# Bi-Quad_Filter.net
KiCad netlist of a schematic drawn in EAGLE
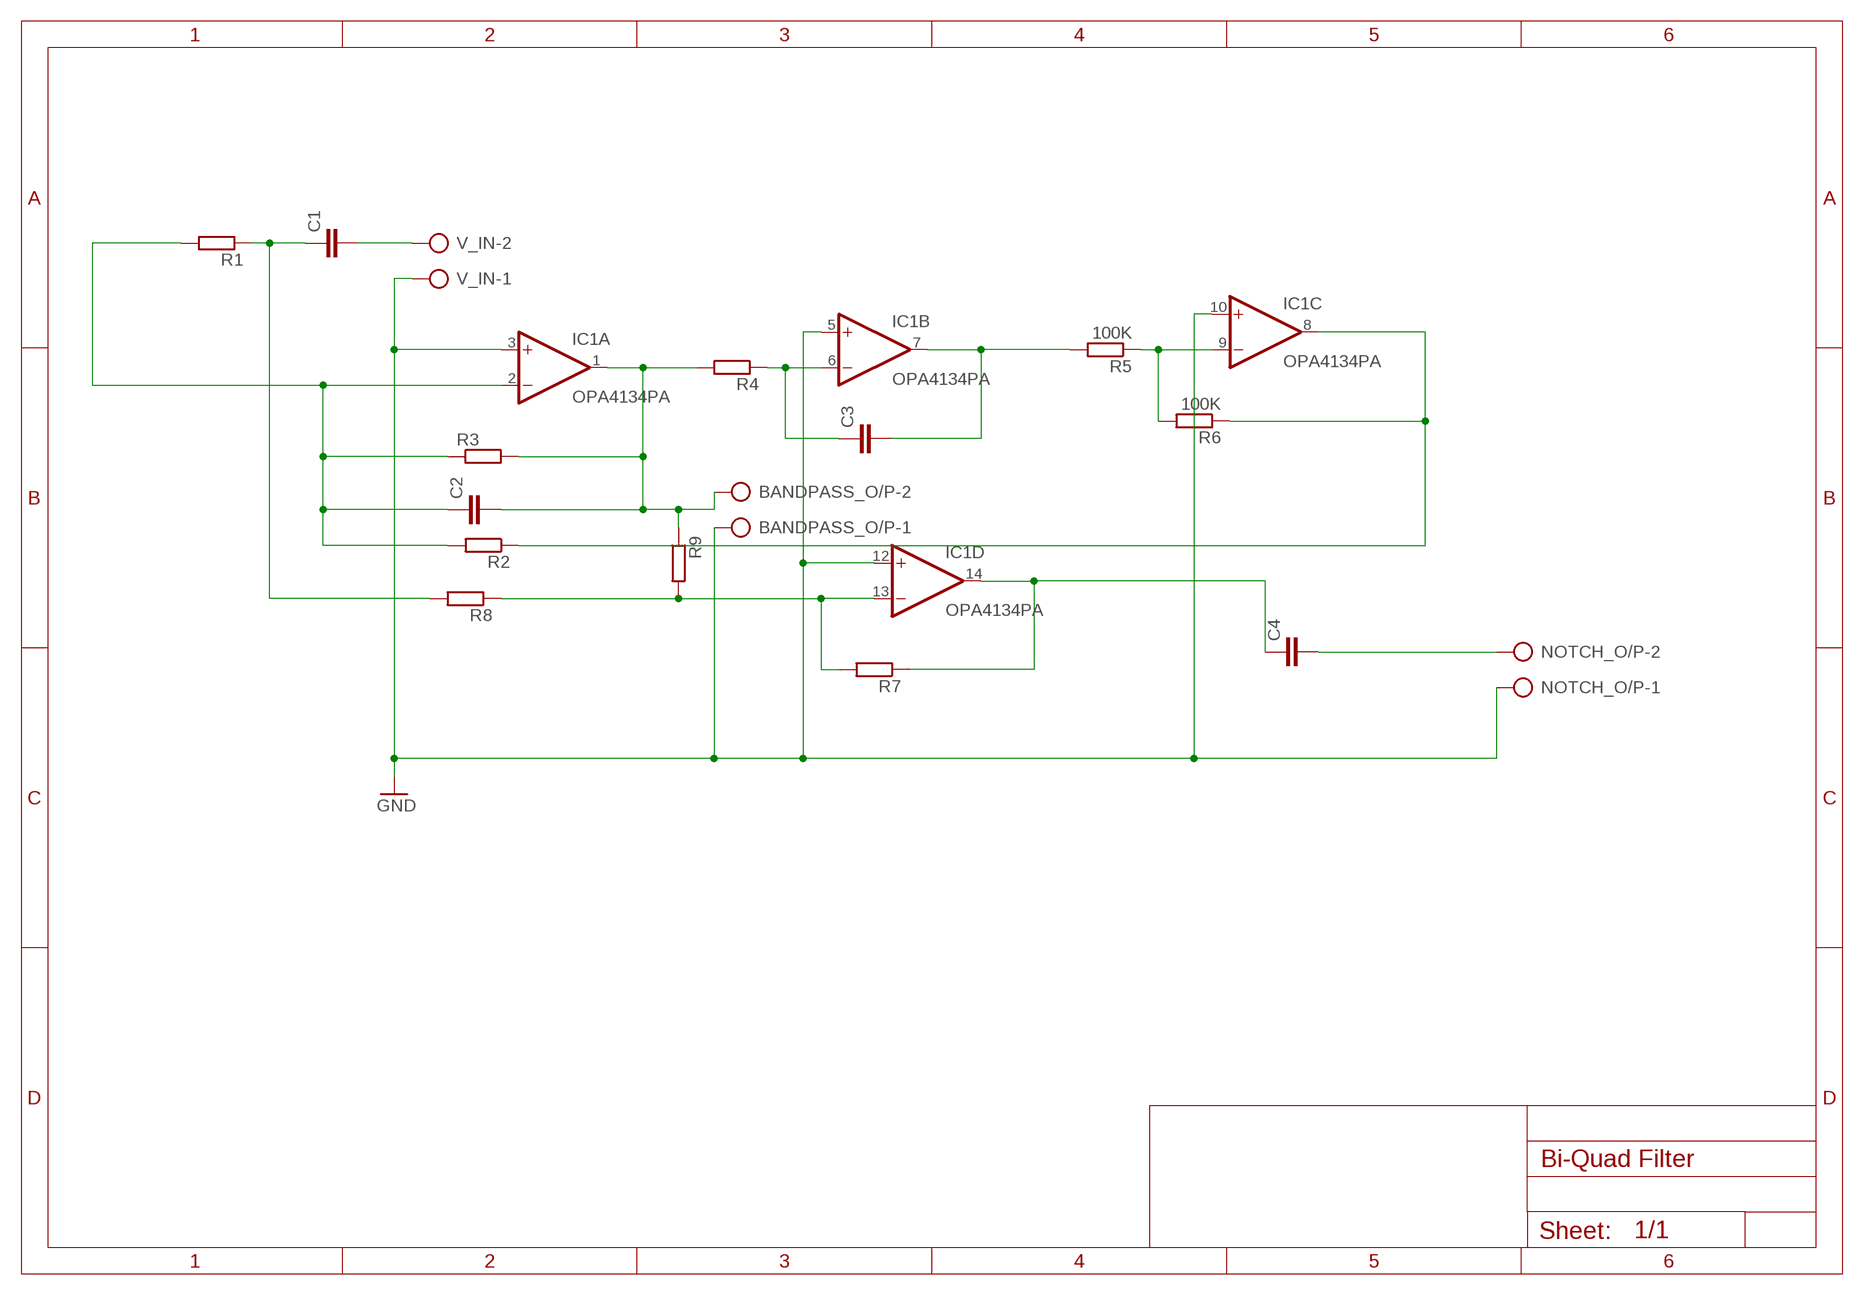
[diagram p0: schematic, sheet 1]

(export (version "E")
  (design (tool "Eeschema 10.0.6"))
  (components
    (comp (ref "BANDPASS_O/P")
      (value "AK300/2")
      (footprint "eagle-import:AK300_2")
      (libsource (lib "eagle-import") (part "AK300/2"))
    )
    (comp (ref "C1")
      (value "C-EU050-024X044")
      (footprint "eagle-import:C050-024X044")
      (libsource (lib "eagle-import") (part "C-EU050-024X044"))
    )
    (comp (ref "C2")
      (value "C-EU050-024X044")
      (footprint "eagle-import:C050-024X044")
      (libsource (lib "eagle-import") (part "C-EU050-024X044"))
    )
    (comp (ref "C3")
      (value "C-EU050-024X044")
      (footprint "eagle-import:C050-024X044")
      (libsource (lib "eagle-import") (part "C-EU050-024X044"))
    )
    (comp (ref "C4")
      (value "C-EU050-024X044")
      (footprint "eagle-import:C050-024X044")
      (libsource (lib "eagle-import") (part "C-EU050-024X044"))
    )
    (comp (ref "IC1")
      (value "OPA4134PA")
      (footprint "eagle-import:DIL14")
      (libsource (lib "eagle-import") (part "OPA4PA134"))
    )
    (comp (ref "NOTCH_O/P")
      (value "AK300/2")
      (footprint "eagle-import:AK300_2")
      (libsource (lib "eagle-import") (part "AK300/2"))
    )
    (comp (ref "R1")
      (value "R-EU_0204/5")
      (footprint "eagle-import:0204_5")
      (libsource (lib "eagle-import") (part "R-EU_0204/5"))
    )
    (comp (ref "R2")
      (value "R-EU_0204/5")
      (footprint "eagle-import:0204_5")
      (libsource (lib "eagle-import") (part "R-EU_0204/5"))
    )
    (comp (ref "R3")
      (value "R-EU_0204/5")
      (footprint "eagle-import:0204_5")
      (libsource (lib "eagle-import") (part "R-EU_0204/5"))
    )
    (comp (ref "R4")
      (value "R-EU_0204/5")
      (footprint "eagle-import:0204_5")
      (libsource (lib "eagle-import") (part "R-EU_0204/5"))
    )
    (comp (ref "R5")
      (value "100K")
      (footprint "eagle-import:0204_5")
      (libsource (lib "eagle-import") (part "R-EU_0204/5"))
    )
    (comp (ref "R6")
      (value "100K")
      (footprint "eagle-import:0204_5")
      (libsource (lib "eagle-import") (part "R-EU_0204/5"))
    )
    (comp (ref "R7")
      (value "R-EU_0204/5")
      (footprint "eagle-import:0204_5")
      (libsource (lib "eagle-import") (part "R-EU_0204/5"))
    )
    (comp (ref "R8")
      (value "R-EU_0204/5")
      (footprint "eagle-import:0204_5")
      (libsource (lib "eagle-import") (part "R-EU_0204/5"))
    )
    (comp (ref "R9")
      (value "R-EU_0204/5")
      (footprint "eagle-import:0204_5")
      (libsource (lib "eagle-import") (part "R-EU_0204/5"))
    )
    (comp (ref "V_IN")
      (value "AK300/2")
      (footprint "eagle-import:AK300_2")
      (libsource (lib "eagle-import") (part "AK300/2"))
    )
  )
  (nets
    (net (code "1") (name "GND") (class "Default")
      (node (ref "BANDPASS_O/P") (pin "1") (pinfunction "KL_1") (pintype "passive"))
      (node (ref "IC1") (pin "10") (pinfunction "+IN_10") (pintype "input"))
      (node (ref "IC1") (pin "12") (pinfunction "+IN_12") (pintype "input"))
      (node (ref "IC1") (pin "3") (pinfunction "+IN_3") (pintype "input"))
      (node (ref "IC1") (pin "5") (pinfunction "+IN_5") (pintype "input"))
      (node (ref "NOTCH_O/P") (pin "1") (pinfunction "KL_1") (pintype "passive"))
      (node (ref "V_IN") (pin "1") (pinfunction "KL_1") (pintype "passive"))
    )
    (net (code "2") (name "Net-(BANDPASS_O/PB-KL)") (class "Default")
      (node (ref "BANDPASS_O/P") (pin "2") (pinfunction "KL_2") (pintype "passive"))
      (node (ref "C2") (pin "2") (pinfunction "2_2") (pintype "passive"))
      (node (ref "IC1") (pin "1") (pinfunction "OUT_1") (pintype "output"))
      (node (ref "R3") (pin "2") (pinfunction "2_2") (pintype "passive"))
      (node (ref "R4") (pin "2") (pinfunction "2_2") (pintype "passive"))
      (node (ref "R9") (pin "1") (pinfunction "1_1") (pintype "passive"))
    )
    (net (code "3") (name "Net-(C1-Pad1)") (class "Default")
      (node (ref "C1") (pin "1") (pinfunction "1_1") (pintype "passive"))
      (node (ref "R1") (pin "1") (pinfunction "1_1") (pintype "passive"))
      (node (ref "R8") (pin "2") (pinfunction "2_2") (pintype "passive"))
    )
    (net (code "4") (name "Net-(IC1A--IN)") (class "Default")
      (node (ref "C2") (pin "1") (pinfunction "1_1") (pintype "passive"))
      (node (ref "IC1") (pin "2") (pinfunction "-IN_2") (pintype "input"))
      (node (ref "R1") (pin "2") (pinfunction "2_2") (pintype "passive"))
      (node (ref "R2") (pin "2") (pinfunction "2_2") (pintype "passive"))
      (node (ref "R3") (pin "1") (pinfunction "1_1") (pintype "passive"))
    )
    (net (code "5") (name "Net-(IC1B--IN)") (class "Default")
      (node (ref "C3") (pin "1") (pinfunction "1_1") (pintype "passive"))
      (node (ref "IC1") (pin "6") (pinfunction "-IN_6") (pintype "input"))
      (node (ref "R4") (pin "1") (pinfunction "1_1") (pintype "passive"))
    )
    (net (code "6") (name "Net-(IC1B-OUT)") (class "Default")
      (node (ref "C3") (pin "2") (pinfunction "2_2") (pintype "passive"))
      (node (ref "IC1") (pin "7") (pinfunction "OUT_7") (pintype "output"))
      (node (ref "R5") (pin "2") (pinfunction "2_2") (pintype "passive"))
    )
    (net (code "7") (name "Net-(IC1C--IN)") (class "Default")
      (node (ref "IC1") (pin "9") (pinfunction "-IN_9") (pintype "input"))
      (node (ref "R5") (pin "1") (pinfunction "1_1") (pintype "passive"))
      (node (ref "R6") (pin "2") (pinfunction "2_2") (pintype "passive"))
    )
    (net (code "8") (name "Net-(IC1C-OUT)") (class "Default")
      (node (ref "IC1") (pin "8") (pinfunction "OUT_8") (pintype "output"))
      (node (ref "R2") (pin "1") (pinfunction "1_1") (pintype "passive"))
      (node (ref "R6") (pin "1") (pinfunction "1_1") (pintype "passive"))
    )
    (net (code "9") (name "Net-(IC1D--IN)") (class "Default")
      (node (ref "IC1") (pin "13") (pinfunction "-IN_13") (pintype "input"))
      (node (ref "R7") (pin "2") (pinfunction "2_2") (pintype "passive"))
      (node (ref "R8") (pin "1") (pinfunction "1_1") (pintype "passive"))
      (node (ref "R9") (pin "2") (pinfunction "2_2") (pintype "passive"))
    )
    (net (code "10") (name "Net-(IC1D-OUT)") (class "Default")
      (node (ref "C4") (pin "1") (pinfunction "1_1") (pintype "passive"))
      (node (ref "IC1") (pin "14") (pinfunction "OUT_14") (pintype "output"))
      (node (ref "R7") (pin "1") (pinfunction "1_1") (pintype "passive"))
    )
    (net (code "11") (name "Net-(NOTCH_O/PB-KL)") (class "Default")
      (node (ref "C4") (pin "2") (pinfunction "2_2") (pintype "passive"))
      (node (ref "NOTCH_O/P") (pin "2") (pinfunction "KL_2") (pintype "passive"))
    )
    (net (code "12") (name "Net-(V_INB-KL)") (class "Default")
      (node (ref "C1") (pin "2") (pinfunction "2_2") (pintype "passive"))
      (node (ref "V_IN") (pin "2") (pinfunction "KL_2") (pintype "passive"))
    )
  )
)
